# DC-link-Caps.net
KiCad netlist of a schematic drawn in Altium Designer
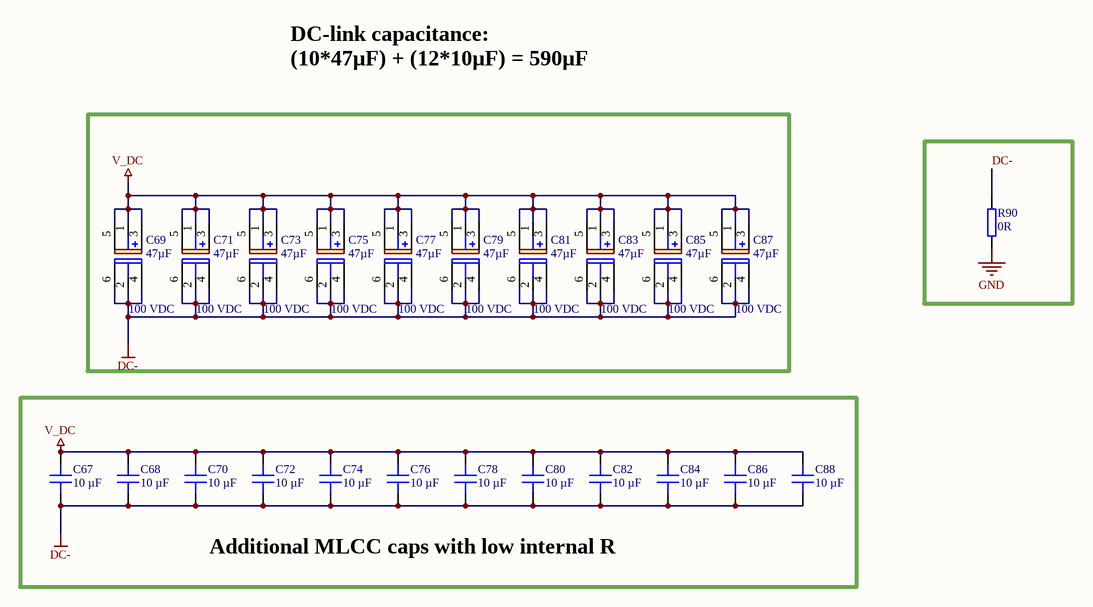
[diagram p0: DC-link-Caps.SchDoc]

(export (version "E")
  (design (tool "Eeschema 10.0.6"))
  (components
    (comp (ref "C67")
      (value "10 µF")
      (footprint "C_1210_N")
      (description "Capacitor 1210, 100 VDC, 10µF, X7S")
      (fields
        (field (name "MANUFACTURER PART NUMBER") "GRM32EC72A106KE05L")
        (field (name "MANUFACTURER") "Murata Electronics")
        (field (name "CREATED FROM") "DHufnagel")
      )
      (libsource (lib "user") (part "Capacitor"))
    )
    (comp (ref "C68")
      (value "10 µF")
      (footprint "C_1210_N")
      (description "Capacitor 1210, 100 VDC, 10µF, X7S")
      (fields
        (field (name "MANUFACTURER PART NUMBER") "GRM32EC72A106KE05L")
        (field (name "MANUFACTURER") "Murata Electronics")
        (field (name "CREATED FROM") "DHufnagel")
      )
      (libsource (lib "user") (part "Capacitor"))
    )
    (comp (ref "C69")
      (value "47µF")
      (footprint "EEEFK0J332AV")
      (description "13.8x12.5x13.8mm, 100 VDC,  47 µF")
      (fields
        (field (name "MANUFACTURER PART NUMBER") "EEEFK2A470AQ")
        (field (name "MANUFACTURER") "Panasonic")
        (field (name "VOLTAGE RATING") "100 VDC")
        (field (name "CREATED FROM") "KIlhan")
      )
      (libsource (lib "user") (part "EEV-FK2A470V"))
    )
    (comp (ref "C70")
      (value "10 µF")
      (footprint "C_1210_N")
      (description "Capacitor 1210, 100 VDC, 10µF, X7S")
      (fields
        (field (name "MANUFACTURER PART NUMBER") "GRM32EC72A106KE05L")
        (field (name "MANUFACTURER") "Murata Electronics")
        (field (name "CREATED FROM") "DHufnagel")
      )
      (libsource (lib "user") (part "Capacitor"))
    )
    (comp (ref "C71")
      (value "47µF")
      (footprint "EEEFK0J332AV")
      (description "13.8x12.5x13.8mm, 100 VDC,  47 µF")
      (fields
        (field (name "MANUFACTURER PART NUMBER") "EEEFK2A470AQ")
        (field (name "MANUFACTURER") "Panasonic")
        (field (name "VOLTAGE RATING") "100 VDC")
        (field (name "CREATED FROM") "KIlhan")
      )
      (libsource (lib "user") (part "EEV-FK2A470V"))
    )
    (comp (ref "C72")
      (value "10 µF")
      (footprint "C_1210_N")
      (description "Capacitor 1210, 100 VDC, 10µF, X7S")
      (fields
        (field (name "MANUFACTURER PART NUMBER") "GRM32EC72A106KE05L")
        (field (name "MANUFACTURER") "Murata Electronics")
        (field (name "CREATED FROM") "DHufnagel")
      )
      (libsource (lib "user") (part "Capacitor"))
    )
    (comp (ref "C73")
      (value "47µF")
      (footprint "EEEFK0J332AV")
      (description "13.8x12.5x13.8mm, 100 VDC,  47 µF")
      (fields
        (field (name "MANUFACTURER PART NUMBER") "EEEFK2A470AQ")
        (field (name "MANUFACTURER") "Panasonic")
        (field (name "VOLTAGE RATING") "100 VDC")
        (field (name "CREATED FROM") "KIlhan")
      )
      (libsource (lib "user") (part "EEV-FK2A470V"))
    )
    (comp (ref "C74")
      (value "10 µF")
      (footprint "C_1210_N")
      (description "Capacitor 1210, 100 VDC, 10µF, X7S")
      (fields
        (field (name "MANUFACTURER PART NUMBER") "GRM32EC72A106KE05L")
        (field (name "MANUFACTURER") "Murata Electronics")
        (field (name "CREATED FROM") "DHufnagel")
      )
      (libsource (lib "user") (part "Capacitor"))
    )
    (comp (ref "C75")
      (value "47µF")
      (footprint "EEEFK0J332AV")
      (description "13.8x12.5x13.8mm, 100 VDC,  47 µF")
      (fields
        (field (name "MANUFACTURER PART NUMBER") "EEEFK2A470AQ")
        (field (name "MANUFACTURER") "Panasonic")
        (field (name "VOLTAGE RATING") "100 VDC")
        (field (name "CREATED FROM") "KIlhan")
      )
      (libsource (lib "user") (part "EEV-FK2A470V"))
    )
    (comp (ref "C76")
      (value "10 µF")
      (footprint "C_1210_N")
      (description "Capacitor 1210, 100 VDC, 10µF, X7S")
      (fields
        (field (name "MANUFACTURER PART NUMBER") "GRM32EC72A106KE05L")
        (field (name "MANUFACTURER") "Murata Electronics")
        (field (name "CREATED FROM") "DHufnagel")
      )
      (libsource (lib "user") (part "Capacitor"))
    )
    (comp (ref "C77")
      (value "47µF")
      (footprint "EEEFK0J332AV")
      (description "13.8x12.5x13.8mm, 100 VDC,  47 µF")
      (fields
        (field (name "MANUFACTURER PART NUMBER") "EEEFK2A470AQ")
        (field (name "MANUFACTURER") "Panasonic")
        (field (name "VOLTAGE RATING") "100 VDC")
        (field (name "CREATED FROM") "KIlhan")
      )
      (libsource (lib "user") (part "EEV-FK2A470V"))
    )
    (comp (ref "C78")
      (value "10 µF")
      (footprint "C_1210_N")
      (description "Capacitor 1210, 100 VDC, 10µF, X7S")
      (fields
        (field (name "MANUFACTURER PART NUMBER") "GRM32EC72A106KE05L")
        (field (name "MANUFACTURER") "Murata Electronics")
        (field (name "CREATED FROM") "DHufnagel")
      )
      (libsource (lib "user") (part "Capacitor"))
    )
    (comp (ref "C79")
      (value "47µF")
      (footprint "EEEFK0J332AV")
      (description "13.8x12.5x13.8mm, 100 VDC,  47 µF")
      (fields
        (field (name "MANUFACTURER PART NUMBER") "EEEFK2A470AQ")
        (field (name "MANUFACTURER") "Panasonic")
        (field (name "VOLTAGE RATING") "100 VDC")
        (field (name "CREATED FROM") "KIlhan")
      )
      (libsource (lib "user") (part "EEV-FK2A470V"))
    )
    (comp (ref "C80")
      (value "10 µF")
      (footprint "C_1210_N")
      (description "Capacitor 1210, 100 VDC, 10µF, X7S")
      (fields
        (field (name "MANUFACTURER PART NUMBER") "GRM32EC72A106KE05L")
        (field (name "MANUFACTURER") "Murata Electronics")
        (field (name "CREATED FROM") "DHufnagel")
      )
      (libsource (lib "user") (part "Capacitor"))
    )
    (comp (ref "C81")
      (value "47µF")
      (footprint "EEEFK0J332AV")
      (description "13.8x12.5x13.8mm, 100 VDC,  47 µF")
      (fields
        (field (name "MANUFACTURER PART NUMBER") "EEEFK2A470AQ")
        (field (name "MANUFACTURER") "Panasonic")
        (field (name "VOLTAGE RATING") "100 VDC")
        (field (name "CREATED FROM") "KIlhan")
      )
      (libsource (lib "user") (part "EEV-FK2A470V"))
    )
    (comp (ref "C82")
      (value "10 µF")
      (footprint "C_1210_N")
      (description "Capacitor 1210, 100 VDC, 10µF, X7S")
      (fields
        (field (name "MANUFACTURER PART NUMBER") "GRM32EC72A106KE05L")
        (field (name "MANUFACTURER") "Murata Electronics")
        (field (name "CREATED FROM") "DHufnagel")
      )
      (libsource (lib "user") (part "Capacitor"))
    )
    (comp (ref "C83")
      (value "47µF")
      (footprint "EEEFK0J332AV")
      (description "13.8x12.5x13.8mm, 100 VDC,  47 µF")
      (fields
        (field (name "MANUFACTURER PART NUMBER") "EEEFK2A470AQ")
        (field (name "MANUFACTURER") "Panasonic")
        (field (name "VOLTAGE RATING") "100 VDC")
        (field (name "CREATED FROM") "KIlhan")
      )
      (libsource (lib "user") (part "EEV-FK2A470V"))
    )
    (comp (ref "C84")
      (value "10 µF")
      (footprint "C_1210_N")
      (description "Capacitor 1210, 100 VDC, 10µF, X7S")
      (fields
        (field (name "MANUFACTURER PART NUMBER") "GRM32EC72A106KE05L")
        (field (name "MANUFACTURER") "Murata Electronics")
        (field (name "CREATED FROM") "DHufnagel")
      )
      (libsource (lib "user") (part "Capacitor"))
    )
    (comp (ref "C85")
      (value "47µF")
      (footprint "EEEFK0J332AV")
      (description "13.8x12.5x13.8mm, 100 VDC,  47 µF")
      (fields
        (field (name "MANUFACTURER PART NUMBER") "EEEFK2A470AQ")
        (field (name "MANUFACTURER") "Panasonic")
        (field (name "VOLTAGE RATING") "100 VDC")
        (field (name "CREATED FROM") "KIlhan")
      )
      (libsource (lib "user") (part "EEV-FK2A470V"))
    )
    (comp (ref "C86")
      (value "10 µF")
      (footprint "C_1210_N")
      (description "Capacitor 1210, 100 VDC, 10µF, X7S")
      (fields
        (field (name "MANUFACTURER PART NUMBER") "GRM32EC72A106KE05L")
        (field (name "MANUFACTURER") "Murata Electronics")
        (field (name "CREATED FROM") "DHufnagel")
      )
      (libsource (lib "user") (part "Capacitor"))
    )
    (comp (ref "C87")
      (value "47µF")
      (footprint "EEEFK0J332AV")
      (description "13.8x12.5x13.8mm, 100 VDC,  47 µF")
      (fields
        (field (name "MANUFACTURER PART NUMBER") "EEEFK2A470AQ")
        (field (name "MANUFACTURER") "Panasonic")
        (field (name "VOLTAGE RATING") "100 VDC")
        (field (name "CREATED FROM") "KIlhan")
      )
      (libsource (lib "user") (part "EEV-FK2A470V"))
    )
    (comp (ref "C88")
      (value "10 µF")
      (footprint "C_1210_N")
      (description "Capacitor 1210, 100 VDC, 10µF, X7S")
      (fields
        (field (name "MANUFACTURER PART NUMBER") "GRM32EC72A106KE05L")
        (field (name "MANUFACTURER") "Murata Electronics")
        (field (name "CREATED FROM") "DHufnagel")
      )
      (libsource (lib "user") (part "Capacitor"))
    )
    (comp (ref "R90")
      (value "0R")
      (footprint "RES 0603_1608")
      (description "SMD resistor E24 series")
      (fields
        (field (name "MANUFACTURER PART NUMBER") "RC0603JR-070RL")
        (field (name "MANUFACTURER") "YAGEO")
        (field (name "CREATED FROM") "MGremer")
      )
      (libsource (lib "user") (part "Resistor"))
    )
  )
  (nets
    (net (code "1") (name "DC-") (class "Default")
      (node (ref "C67") (pin "1") (pinfunction "1_1") (pintype "passive"))
      (node (ref "C68") (pin "1") (pinfunction "1_1") (pintype "passive"))
      (node (ref "C69") (pin "2") (pinfunction "-_1_2") (pintype "passive"))
      (node (ref "C69") (pin "4") (pinfunction "+_3_4") (pintype "passive"))
      (node (ref "C69") (pin "6") (pinfunction "-_3_6") (pintype "passive"))
      (node (ref "C70") (pin "1") (pinfunction "1_1") (pintype "passive"))
      (node (ref "C71") (pin "2") (pinfunction "-_1_2") (pintype "passive"))
      (node (ref "C71") (pin "4") (pinfunction "+_3_4") (pintype "passive"))
      (node (ref "C71") (pin "6") (pinfunction "-_3_6") (pintype "passive"))
      (node (ref "C72") (pin "1") (pinfunction "1_1") (pintype "passive"))
      (node (ref "C73") (pin "2") (pinfunction "-_1_2") (pintype "passive"))
      (node (ref "C73") (pin "4") (pinfunction "+_3_4") (pintype "passive"))
      (node (ref "C73") (pin "6") (pinfunction "-_3_6") (pintype "passive"))
      (node (ref "C74") (pin "1") (pinfunction "1_1") (pintype "passive"))
      (node (ref "C75") (pin "2") (pinfunction "-_1_2") (pintype "passive"))
      (node (ref "C75") (pin "4") (pinfunction "+_3_4") (pintype "passive"))
      (node (ref "C75") (pin "6") (pinfunction "-_3_6") (pintype "passive"))
      (node (ref "C76") (pin "1") (pinfunction "1_1") (pintype "passive"))
      (node (ref "C77") (pin "2") (pinfunction "-_1_2") (pintype "passive"))
      (node (ref "C77") (pin "4") (pinfunction "+_3_4") (pintype "passive"))
      (node (ref "C77") (pin "6") (pinfunction "-_3_6") (pintype "passive"))
      (node (ref "C78") (pin "1") (pinfunction "1_1") (pintype "passive"))
      (node (ref "C79") (pin "2") (pinfunction "-_1_2") (pintype "passive"))
      (node (ref "C79") (pin "4") (pinfunction "+_3_4") (pintype "passive"))
      (node (ref "C79") (pin "6") (pinfunction "-_3_6") (pintype "passive"))
      (node (ref "C80") (pin "1") (pinfunction "1_1") (pintype "passive"))
      (node (ref "C81") (pin "2") (pinfunction "-_1_2") (pintype "passive"))
      (node (ref "C81") (pin "4") (pinfunction "+_3_4") (pintype "passive"))
      (node (ref "C81") (pin "6") (pinfunction "-_3_6") (pintype "passive"))
      (node (ref "C82") (pin "1") (pinfunction "1_1") (pintype "passive"))
      (node (ref "C83") (pin "2") (pinfunction "-_1_2") (pintype "passive"))
      (node (ref "C83") (pin "4") (pinfunction "+_3_4") (pintype "passive"))
      (node (ref "C83") (pin "6") (pinfunction "-_3_6") (pintype "passive"))
      (node (ref "C84") (pin "1") (pinfunction "1_1") (pintype "passive"))
      (node (ref "C85") (pin "2") (pinfunction "-_1_2") (pintype "passive"))
      (node (ref "C85") (pin "4") (pinfunction "+_3_4") (pintype "passive"))
      (node (ref "C85") (pin "6") (pinfunction "-_3_6") (pintype "passive"))
      (node (ref "C86") (pin "1") (pinfunction "1_1") (pintype "passive"))
      (node (ref "C87") (pin "2") (pinfunction "-_1_2") (pintype "passive"))
      (node (ref "C87") (pin "4") (pinfunction "+_3_4") (pintype "passive"))
      (node (ref "C87") (pin "6") (pinfunction "-_3_6") (pintype "passive"))
      (node (ref "C88") (pin "1") (pinfunction "1_1") (pintype "passive"))
      (node (ref "R90") (pin "1") (pinfunction "1_1") (pintype "passive"))
    )
    (net (code "2") (name "GND") (class "Default")
      (node (ref "R90") (pin "2") (pinfunction "2_2") (pintype "passive"))
    )
    (net (code "3") (name "V_DC") (class "Default")
      (node (ref "C67") (pin "2") (pinfunction "2_2") (pintype "passive"))
      (node (ref "C68") (pin "2") (pinfunction "2_2") (pintype "passive"))
      (node (ref "C69") (pin "1") (pinfunction "+_1_1") (pintype "passive"))
      (node (ref "C69") (pin "3") (pinfunction "+_2_3") (pintype "passive"))
      (node (ref "C69") (pin "5") (pinfunction "-_2_5") (pintype "passive"))
      (node (ref "C70") (pin "2") (pinfunction "2_2") (pintype "passive"))
      (node (ref "C71") (pin "1") (pinfunction "+_1_1") (pintype "passive"))
      (node (ref "C71") (pin "3") (pinfunction "+_2_3") (pintype "passive"))
      (node (ref "C71") (pin "5") (pinfunction "-_2_5") (pintype "passive"))
      (node (ref "C72") (pin "2") (pinfunction "2_2") (pintype "passive"))
      (node (ref "C73") (pin "1") (pinfunction "+_1_1") (pintype "passive"))
      (node (ref "C73") (pin "3") (pinfunction "+_2_3") (pintype "passive"))
      (node (ref "C73") (pin "5") (pinfunction "-_2_5") (pintype "passive"))
      (node (ref "C74") (pin "2") (pinfunction "2_2") (pintype "passive"))
      (node (ref "C75") (pin "1") (pinfunction "+_1_1") (pintype "passive"))
      (node (ref "C75") (pin "3") (pinfunction "+_2_3") (pintype "passive"))
      (node (ref "C75") (pin "5") (pinfunction "-_2_5") (pintype "passive"))
      (node (ref "C76") (pin "2") (pinfunction "2_2") (pintype "passive"))
      (node (ref "C77") (pin "1") (pinfunction "+_1_1") (pintype "passive"))
      (node (ref "C77") (pin "3") (pinfunction "+_2_3") (pintype "passive"))
      (node (ref "C77") (pin "5") (pinfunction "-_2_5") (pintype "passive"))
      (node (ref "C78") (pin "2") (pinfunction "2_2") (pintype "passive"))
      (node (ref "C79") (pin "1") (pinfunction "+_1_1") (pintype "passive"))
      (node (ref "C79") (pin "3") (pinfunction "+_2_3") (pintype "passive"))
      (node (ref "C79") (pin "5") (pinfunction "-_2_5") (pintype "passive"))
      (node (ref "C80") (pin "2") (pinfunction "2_2") (pintype "passive"))
      (node (ref "C81") (pin "1") (pinfunction "+_1_1") (pintype "passive"))
      (node (ref "C81") (pin "3") (pinfunction "+_2_3") (pintype "passive"))
      (node (ref "C81") (pin "5") (pinfunction "-_2_5") (pintype "passive"))
      (node (ref "C82") (pin "2") (pinfunction "2_2") (pintype "passive"))
      (node (ref "C83") (pin "1") (pinfunction "+_1_1") (pintype "passive"))
      (node (ref "C83") (pin "3") (pinfunction "+_2_3") (pintype "passive"))
      (node (ref "C83") (pin "5") (pinfunction "-_2_5") (pintype "passive"))
      (node (ref "C84") (pin "2") (pinfunction "2_2") (pintype "passive"))
      (node (ref "C85") (pin "1") (pinfunction "+_1_1") (pintype "passive"))
      (node (ref "C85") (pin "3") (pinfunction "+_2_3") (pintype "passive"))
      (node (ref "C85") (pin "5") (pinfunction "-_2_5") (pintype "passive"))
      (node (ref "C86") (pin "2") (pinfunction "2_2") (pintype "passive"))
      (node (ref "C87") (pin "1") (pinfunction "+_1_1") (pintype "passive"))
      (node (ref "C87") (pin "3") (pinfunction "+_2_3") (pintype "passive"))
      (node (ref "C87") (pin "5") (pinfunction "-_2_5") (pintype "passive"))
      (node (ref "C88") (pin "2") (pinfunction "2_2") (pintype "passive"))
    )
  )
)
